# zzh.net
KiCad netlist of a schematic drawn in EAGLE
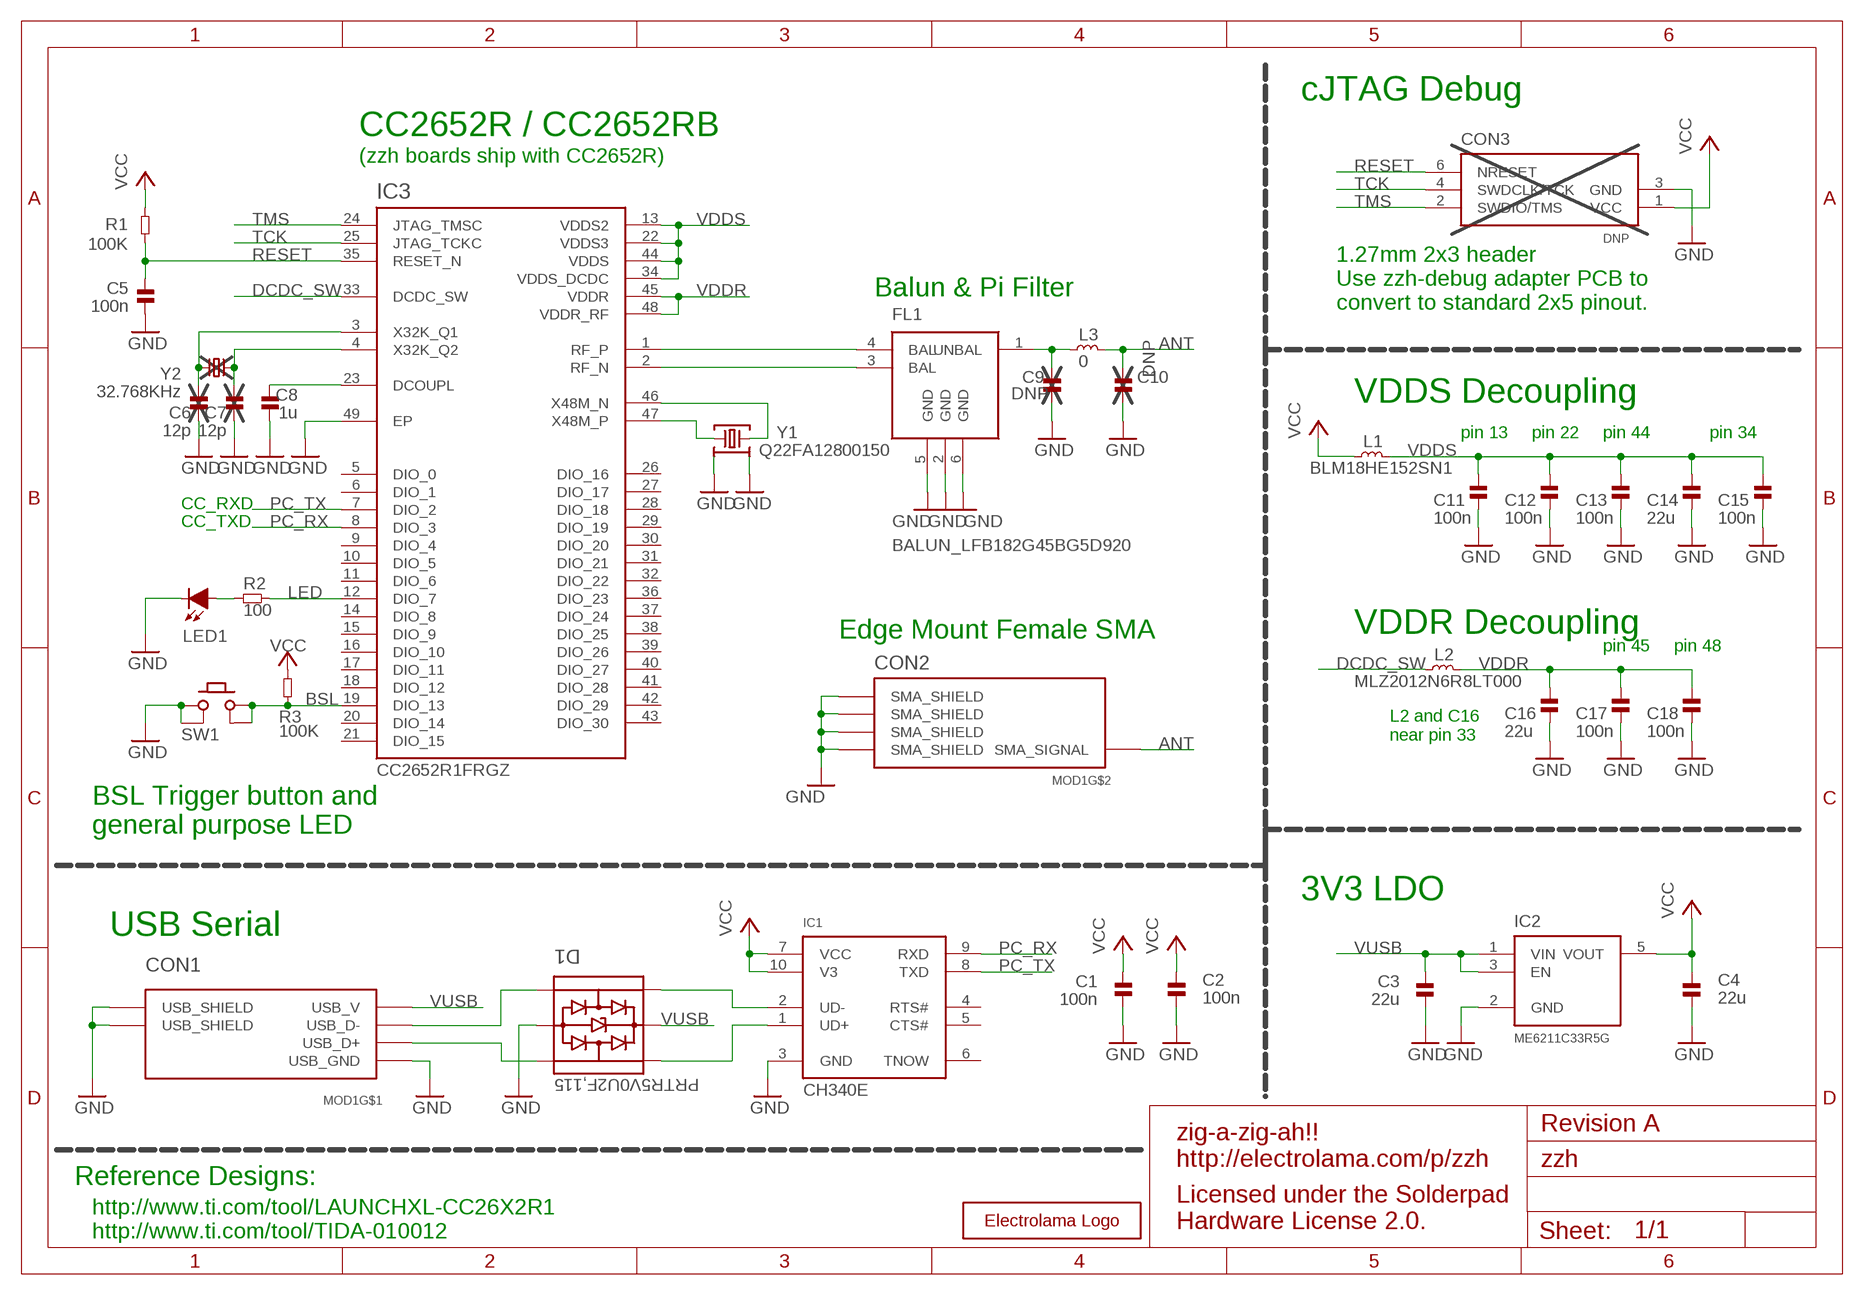
[diagram p0: schematic, sheet 1]

(export (version "E")
  (design (tool "Eeschema 10.0.6"))
  (components
    (comp (ref "C1")
      (value "100n")
      (footprint "eagle-import:_PKG_C_0402")
      (libsource (lib "eagle-import") (part "CAP-0402"))
    )
    (comp (ref "C2")
      (value "100n")
      (footprint "eagle-import:_PKG_C_0402")
      (libsource (lib "eagle-import") (part "CAP-0402"))
    )
    (comp (ref "C3")
      (value "22u")
      (footprint "eagle-import:_PKG_C_0805")
      (libsource (lib "eagle-import") (part "CAP-0805"))
    )
    (comp (ref "C4")
      (value "22u")
      (footprint "eagle-import:_PKG_C_0805")
      (libsource (lib "eagle-import") (part "CAP-0805"))
    )
    (comp (ref "C5")
      (value "100n")
      (footprint "eagle-import:_PKG_C_0402")
      (libsource (lib "eagle-import") (part "CAP-0402"))
    )
    (comp (ref "C6")
      (value "12p")
      (footprint "eagle-import:_PKG_C_0402")
      (libsource (lib "eagle-import") (part "CAP-0402"))
    )
    (comp (ref "C7")
      (value "12p")
      (footprint "eagle-import:_PKG_C_0402")
      (libsource (lib "eagle-import") (part "CAP-0402"))
    )
    (comp (ref "C8")
      (value "1u")
      (footprint "eagle-import:_PKG_C_0402")
      (libsource (lib "eagle-import") (part "CAP-0402"))
    )
    (comp (ref "C9")
      (value "DNP")
      (footprint "eagle-import:_PKG_C_0402")
      (libsource (lib "eagle-import") (part "CAP-0402"))
    )
    (comp (ref "C10")
      (value "DNP")
      (footprint "eagle-import:_PKG_C_0402")
      (libsource (lib "eagle-import") (part "CAP-0402"))
    )
    (comp (ref "C11")
      (value "100n")
      (footprint "eagle-import:_PKG_C_0402")
      (libsource (lib "eagle-import") (part "CAP-0402"))
    )
    (comp (ref "C12")
      (value "100n")
      (footprint "eagle-import:_PKG_C_0402")
      (libsource (lib "eagle-import") (part "CAP-0402"))
    )
    (comp (ref "C13")
      (value "100n")
      (footprint "eagle-import:_PKG_C_0402")
      (libsource (lib "eagle-import") (part "CAP-0402"))
    )
    (comp (ref "C14")
      (value "22u")
      (footprint "eagle-import:_PKG_C_0805")
      (libsource (lib "eagle-import") (part "CAP-0805"))
    )
    (comp (ref "C15")
      (value "100n")
      (footprint "eagle-import:_PKG_C_0402")
      (libsource (lib "eagle-import") (part "CAP-0402"))
    )
    (comp (ref "C16")
      (value "22u")
      (footprint "eagle-import:_PKG_C_0805")
      (libsource (lib "eagle-import") (part "CAP-0805"))
    )
    (comp (ref "C17")
      (value "100n")
      (footprint "eagle-import:_PKG_C_0402")
      (libsource (lib "eagle-import") (part "CAP-0402"))
    )
    (comp (ref "C18")
      (value "100n")
      (footprint "eagle-import:_PKG_C_0402")
      (libsource (lib "eagle-import") (part "CAP-0402"))
    )
    (comp (ref "CON3")
      (value "DNP")
      (footprint "eagle-import:DEBUG_CORTEX_5PIN")
      (libsource (lib "eagle-import") (part "DEBUG_CORTEX-SWD/CJTAG-5PIN-CUT5"))
    )
    (comp (ref "D1")
      (value "PRTR5V0U2F,115")
      (footprint "eagle-import:_PKG_SOT886_JEDEC-MO-252")
      (fields
        (field (name "MOUSER_PART_NUMBER") "771-PRTR5V0U2F-T/R")
        (field (name "RS_PART_NUMBER") "8166931P")
      )
      (libsource (lib "eagle-import") (part "DIODE-TVS-PRTR5V0U2F{dblquote}"))
    )
    (comp (ref "FL1")
      (value "BALUN_LFB182G45BG5D920")
      (footprint "eagle-import:LFB182G45BG5D920")
      (fields
        (field (name "MANUFACTURER_PART_NUMBER") "LFB182G45BG5D920")
        (field (name "MOUSER_PART_NUMBER") "81-LFB182G45BG5D920")
      )
      (libsource (lib "eagle-import") (part "BALUN_LFB182G45BG5D920"))
    )
    (comp (ref "IC1")
      (value "CH340E")
      (footprint "eagle-import:_PKG_MSOP10_TI-DGS10")
      (libsource (lib "eagle-import") (part "INTERFACE-CH340E"))
    )
    (comp (ref "IC2")
      (value "ME6211C33R5G")
      (footprint "eagle-import:SOT65P212X110-5N")
      (libsource (lib "eagle-import") (part "POWER-LDO-ME6211C33R5G"))
    )
    (comp (ref "IC3")
      (value "CC2652R1FRGZ")
      (footprint "eagle-import:QFN50P700X700X100-49N")
      (fields
        (field (name "MANUFACTURER_PART_NUMBER") "CC2652R1FRGZT")
        (field (name "MOUSER_PART_NUMBER") "595-CC2652R1FRGZT")
      )
      (libsource (lib "eagle-import") (part "WMCU-CC2652R1FRGZ"))
    )
    (comp (ref "L1")
      (value "BLM18HE152SN1")
      (footprint "eagle-import:_PKG_L_0603")
      (libsource (lib "eagle-import") (part "INDUCTOR-0603"))
    )
    (comp (ref "L2")
      (value "MLZ2012N6R8LT000")
      (footprint "eagle-import:_PKG_C_0805")
      (libsource (lib "eagle-import") (part "INDUCTOR-0805"))
    )
    (comp (ref "L3")
      (value "0")
      (footprint "eagle-import:_PKG_L_0402")
      (libsource (lib "eagle-import") (part "INDUCTOR-0402"))
    )
    (comp (ref "LED1")
      (value "LED-0603")
      (footprint "eagle-import:_PKG_LED_0603")
      (libsource (lib "eagle-import") (part "LED-0603"))
    )
    (comp (ref "MOD1")
      (value "ZZH_MODULE")
      (footprint "eagle-import:ZZH_MODULE")
      (libsource (lib "eagle-import") (part "ZZH_MODULE"))
    )
    (comp (ref "R1")
      (value "100K")
      (footprint "eagle-import:_PKG_C_0402")
      (libsource (lib "eagle-import") (part "RES-0402"))
    )
    (comp (ref "R2")
      (value "100")
      (footprint "eagle-import:_PKG_C_0402")
      (libsource (lib "eagle-import") (part "RES-0402"))
    )
    (comp (ref "R3")
      (value "100K")
      (footprint "eagle-import:_PKG_C_0402")
      (libsource (lib "eagle-import") (part "RES-0402"))
    )
    (comp (ref "SW1")
      (value "K2-1177SW-D4DW-06")
      (footprint "eagle-import:K2-1177SW-D4DW-06")
      (libsource (lib "eagle-import") (part "PUSHBUTTON-K2-1177SW-D4DW-06"))
    )
    (comp (ref "U$5")
      (value "LOGO-ELECTROLAMA")
      (footprint "eagle-import:ELECTROLAMA")
      (libsource (lib "eagle-import") (part "LOGO-ELECTROLAMA"))
    )
    (comp (ref "Y1")
      (value "Q22FA12800150")
      (footprint "eagle-import:XTAL-4P-2016")
      (fields (field (name "DIGIKEY_PART") "1253-2042-1-ND") (field (name "MFG_PART") "CX2016DB48000C0FPLC1"))
      (libsource (lib "eagle-import") (part "48.000MHZ_CX2016DB48000C0FPLC1"))
    )
    (comp (ref "Y2")
      (value "32.768KHz")
      (footprint "eagle-import:XTAL-2P-3215")
      (fields (field (name "LCSC_PART") "C32346") (field (name "MFG_PART") "Q13FC1350000400"))
      (libsource (lib "eagle-import") (part "32.768KHZ_Q13FC1350000400"))
    )
  )
  (nets
    (net (code "1") (name "/ANT") (class "Default")
      (node (ref "C10") (pin "2") (pinfunction "2_2") (pintype "passive"))
      (node (ref "L3") (pin "2") (pinfunction "2_2") (pintype "passive"))
      (node (ref "MOD1") (pin "SMA_SIGNAL") (pinfunction "SMA_SIGNAL_SMA_SIGNAL") (pintype "bidirectional"))
    )
    (net (code "2") (name "/BSL") (class "Default")
      (node (ref "IC3") (pin "19") (pinfunction "DIO_13_19") (pintype "bidirectional"))
      (node (ref "R3") (pin "2") (pinfunction "2_2") (pintype "passive"))
      (node (ref "SW1") (pin "3") (pinfunction "2_1_3") (pintype "bidirectional"))
      (node (ref "SW1") (pin "4") (pinfunction "2_2_4") (pintype "bidirectional"))
    )
    (net (code "3") (name "/DCDC_SW") (class "Default")
      (node (ref "IC3") (pin "33") (pinfunction "DCDC_SW_33") (pintype "bidirectional"))
      (node (ref "L2") (pin "1") (pinfunction "1_1") (pintype "passive"))
    )
    (net (code "4") (name "/LED") (class "Default")
      (node (ref "IC3") (pin "12") (pinfunction "DIO_7_12") (pintype "bidirectional"))
      (node (ref "R2") (pin "1") (pinfunction "1_1") (pintype "passive"))
    )
    (net (code "5") (name "/PC_RX") (class "Default")
      (node (ref "IC1") (pin "9") (pinfunction "RXD_9") (pintype "bidirectional"))
      (node (ref "IC3") (pin "8") (pinfunction "DIO_3_8") (pintype "bidirectional"))
    )
    (net (code "6") (name "/PC_TX") (class "Default")
      (node (ref "IC1") (pin "8") (pinfunction "TXD_8") (pintype "bidirectional"))
      (node (ref "IC3") (pin "7") (pinfunction "DIO_2_7") (pintype "bidirectional"))
    )
    (net (code "7") (name "/RESET") (class "Default")
      (node (ref "C5") (pin "2") (pinfunction "2_2") (pintype "passive"))
      (node (ref "CON3") (pin "6") (pinfunction "NRESET_6") (pintype "bidirectional"))
      (node (ref "IC3") (pin "35") (pinfunction "RESET_N_35") (pintype "bidirectional"))
      (node (ref "R1") (pin "1") (pinfunction "1_1") (pintype "passive"))
    )
    (net (code "8") (name "/TCK") (class "Default")
      (node (ref "CON3") (pin "4") (pinfunction "SWDCLK/TCK_4") (pintype "bidirectional"))
      (node (ref "IC3") (pin "25") (pinfunction "JTAG_TCKC_25") (pintype "bidirectional"))
    )
    (net (code "9") (name "/TMS") (class "Default")
      (node (ref "CON3") (pin "2") (pinfunction "SWDIO/TMS_2") (pintype "bidirectional"))
      (node (ref "IC3") (pin "24") (pinfunction "JTAG_TMSC_24") (pintype "bidirectional"))
    )
    (net (code "10") (name "/VDDR") (class "Default")
      (node (ref "C16") (pin "1") (pinfunction "1_1") (pintype "passive"))
      (node (ref "C17") (pin "1") (pinfunction "1_1") (pintype "passive"))
      (node (ref "C18") (pin "1") (pinfunction "1_1") (pintype "passive"))
      (node (ref "IC3") (pin "45") (pinfunction "VDDR_45") (pintype "bidirectional"))
      (node (ref "IC3") (pin "48") (pinfunction "VDDR_RF_48") (pintype "bidirectional"))
      (node (ref "L2") (pin "2") (pinfunction "2_2") (pintype "passive"))
    )
    (net (code "11") (name "/VDDS") (class "Default")
      (node (ref "C11") (pin "1") (pinfunction "1_1") (pintype "passive"))
      (node (ref "C12") (pin "1") (pinfunction "1_1") (pintype "passive"))
      (node (ref "C13") (pin "1") (pinfunction "1_1") (pintype "passive"))
      (node (ref "C14") (pin "1") (pinfunction "1_1") (pintype "passive"))
      (node (ref "C15") (pin "1") (pinfunction "1_1") (pintype "passive"))
      (node (ref "IC3") (pin "13") (pinfunction "VDDS2_13") (pintype "bidirectional"))
      (node (ref "IC3") (pin "22") (pinfunction "VDDS3_22") (pintype "bidirectional"))
      (node (ref "IC3") (pin "34") (pinfunction "VDDS_DCDC_34") (pintype "bidirectional"))
      (node (ref "IC3") (pin "44") (pinfunction "VDDS_44") (pintype "bidirectional"))
      (node (ref "L1") (pin "2") (pinfunction "2_2") (pintype "passive"))
    )
    (net (code "12") (name "/VUSB") (class "Default")
      (node (ref "C3") (pin "1") (pinfunction "1_1") (pintype "passive"))
      (node (ref "D1") (pin "5") (pinfunction "5_5") (pintype "passive"))
      (node (ref "IC2") (pin "1") (pinfunction "VIN_1") (pintype "bidirectional"))
      (node (ref "IC2") (pin "3") (pinfunction "EN_3") (pintype "bidirectional"))
      (node (ref "MOD1") (pin "USB_V") (pinfunction "USB_V_USB_V") (pintype "bidirectional"))
    )
    (net (code "13") (name "GND") (class "Default")
      (node (ref "C1") (pin "1") (pinfunction "1_1") (pintype "passive"))
      (node (ref "C10") (pin "1") (pinfunction "1_1") (pintype "passive"))
      (node (ref "C11") (pin "2") (pinfunction "2_2") (pintype "passive"))
      (node (ref "C12") (pin "2") (pinfunction "2_2") (pintype "passive"))
      (node (ref "C13") (pin "2") (pinfunction "2_2") (pintype "passive"))
      (node (ref "C14") (pin "2") (pinfunction "2_2") (pintype "passive"))
      (node (ref "C15") (pin "2") (pinfunction "2_2") (pintype "passive"))
      (node (ref "C16") (pin "2") (pinfunction "2_2") (pintype "passive"))
      (node (ref "C17") (pin "2") (pinfunction "2_2") (pintype "passive"))
      (node (ref "C18") (pin "2") (pinfunction "2_2") (pintype "passive"))
      (node (ref "C2") (pin "1") (pinfunction "1_1") (pintype "passive"))
      (node (ref "C3") (pin "2") (pinfunction "2_2") (pintype "passive"))
      (node (ref "C4") (pin "2") (pinfunction "2_2") (pintype "passive"))
      (node (ref "C5") (pin "1") (pinfunction "1_1") (pintype "passive"))
      (node (ref "C6") (pin "1") (pinfunction "1_1") (pintype "passive"))
      (node (ref "C7") (pin "1") (pinfunction "1_1") (pintype "passive"))
      (node (ref "C8") (pin "1") (pinfunction "1_1") (pintype "passive"))
      (node (ref "C9") (pin "1") (pinfunction "1_1") (pintype "passive"))
      (node (ref "CON3") (pin "3") (pinfunction "GND_3") (pintype "bidirectional"))
      (node (ref "D1") (pin "2") (pinfunction "2_2") (pintype "passive"))
      (node (ref "FL1") (pin "2") (pinfunction "GND_2") (pintype "bidirectional"))
      (node (ref "FL1") (pin "5") (pinfunction "GND_5") (pintype "bidirectional"))
      (node (ref "FL1") (pin "6") (pinfunction "GND_6") (pintype "bidirectional"))
      (node (ref "IC1") (pin "3") (pinfunction "GND_3") (pintype "bidirectional"))
      (node (ref "IC2") (pin "2") (pinfunction "GND_2") (pintype "bidirectional"))
      (node (ref "IC3") (pin "49") (pinfunction "EP_49") (pintype "bidirectional"))
      (node (ref "LED1") (pin "C") (pinfunction "C_C") (pintype "passive"))
      (node (ref "MOD1") (pin "SMA_SHIELD_1") (pinfunction "SMA_SHIELD_SMA_SHIELD_1") (pintype "bidirectional"))
      (node (ref "MOD1") (pin "SMA_SHIELD_2") (pinfunction "SMA_SHIELD_SMA_SHIELD_2") (pintype "bidirectional"))
      (node (ref "MOD1") (pin "SMA_SHIELD_3") (pinfunction "SMA_SHIELD_SMA_SHIELD_3") (pintype "bidirectional"))
      (node (ref "MOD1") (pin "SMA_SHIELD_4") (pinfunction "SMA_SHIELD_SMA_SHIELD_4") (pintype "bidirectional"))
      (node (ref "MOD1") (pin "USB_GND") (pinfunction "USB_GND_USB_GND") (pintype "bidirectional"))
      (node (ref "MOD1") (pin "USB_SHIELD_1") (pinfunction "USB_SHIELD_USB_SHIELD_1") (pintype "bidirectional"))
      (node (ref "MOD1") (pin "USB_SHIELD_2") (pinfunction "USB_SHIELD_USB_SHIELD_2") (pintype "bidirectional"))
      (node (ref "SW1") (pin "1") (pinfunction "1_1_1") (pintype "bidirectional"))
      (node (ref "SW1") (pin "2") (pinfunction "1_2_2") (pintype "bidirectional"))
      (node (ref "Y1") (pin "2") (pinfunction "2_2") (pintype "bidirectional"))
      (node (ref "Y1") (pin "4") (pinfunction "4_4") (pintype "bidirectional"))
    )
    (net (code "14") (name "Net-(D1-Pad1)") (class "Default")
      (node (ref "D1") (pin "1") (pinfunction "1_1") (pintype "passive"))
      (node (ref "MOD1") (pin "USB_D+") (pinfunction "USB_D+_USB_D+") (pintype "bidirectional"))
    )
    (net (code "15") (name "Net-(D1-Pad3)") (class "Default")
      (node (ref "D1") (pin "3") (pinfunction "3_3") (pintype "passive"))
      (node (ref "MOD1") (pin "USB_D-") (pinfunction "USB_D-_USB_D-") (pintype "bidirectional"))
    )
    (net (code "16") (name "Net-(FL1-UNBAL)") (class "Default")
      (node (ref "C9") (pin "2") (pinfunction "2_2") (pintype "passive"))
      (node (ref "FL1") (pin "1") (pinfunction "UNBAL_1") (pintype "bidirectional"))
      (node (ref "L3") (pin "1") (pinfunction "1_1") (pintype "passive"))
    )
    (net (code "17") (name "Net-(IC1-UD+)") (class "Default")
      (node (ref "D1") (pin "6") (pinfunction "6_6") (pintype "passive"))
      (node (ref "IC1") (pin "1") (pinfunction "UD+_1") (pintype "bidirectional"))
    )
    (net (code "18") (name "Net-(IC1-UD-)") (class "Default")
      (node (ref "D1") (pin "4") (pinfunction "4_4") (pintype "passive"))
      (node (ref "IC1") (pin "2") (pinfunction "UD-_2") (pintype "bidirectional"))
    )
    (net (code "19") (name "Net-(IC3-DCOUPL)") (class "Default")
      (node (ref "C8") (pin "2") (pinfunction "2_2") (pintype "passive"))
      (node (ref "IC3") (pin "23") (pinfunction "DCOUPL_23") (pintype "bidirectional"))
    )
    (net (code "20") (name "Net-(IC3-RF_N)") (class "Default")
      (node (ref "FL1") (pin "3") (pinfunction "BAL_3") (pintype "bidirectional"))
      (node (ref "IC3") (pin "2") (pinfunction "RF_N_2") (pintype "bidirectional"))
    )
    (net (code "21") (name "Net-(IC3-RF_P)") (class "Default")
      (node (ref "FL1") (pin "4") (pinfunction "BAL_4") (pintype "bidirectional"))
      (node (ref "IC3") (pin "1") (pinfunction "RF_P_1") (pintype "bidirectional"))
    )
    (net (code "22") (name "Net-(IC3-X32K_Q1)") (class "Default")
      (node (ref "C6") (pin "2") (pinfunction "2_2") (pintype "passive"))
      (node (ref "IC3") (pin "3") (pinfunction "X32K_Q1_3") (pintype "bidirectional"))
      (node (ref "Y2") (pin "1") (pinfunction "1_1") (pintype "passive"))
    )
    (net (code "23") (name "Net-(IC3-X32K_Q2)") (class "Default")
      (node (ref "C7") (pin "2") (pinfunction "2_2") (pintype "passive"))
      (node (ref "IC3") (pin "4") (pinfunction "X32K_Q2_4") (pintype "bidirectional"))
      (node (ref "Y2") (pin "2") (pinfunction "2_2") (pintype "passive"))
    )
    (net (code "24") (name "Net-(IC3-X48M_N)") (class "Default")
      (node (ref "IC3") (pin "46") (pinfunction "X48M_N_46") (pintype "bidirectional"))
      (node (ref "Y1") (pin "3") (pinfunction "3_3") (pintype "passive"))
    )
    (net (code "25") (name "Net-(IC3-X48M_P)") (class "Default")
      (node (ref "IC3") (pin "47") (pinfunction "X48M_P_47") (pintype "bidirectional"))
      (node (ref "Y1") (pin "1") (pinfunction "1_1") (pintype "passive"))
    )
    (net (code "26") (name "Net-(LED1-PadA)") (class "Default")
      (node (ref "LED1") (pin "A") (pinfunction "A_A") (pintype "passive"))
      (node (ref "R2") (pin "2") (pinfunction "2_2") (pintype "passive"))
    )
    (net (code "27") (name "VCC") (class "Default")
      (node (ref "C1") (pin "2") (pinfunction "2_2") (pintype "passive"))
      (node (ref "C2") (pin "2") (pinfunction "2_2") (pintype "passive"))
      (node (ref "C4") (pin "1") (pinfunction "1_1") (pintype "passive"))
      (node (ref "CON3") (pin "1") (pinfunction "VCC_1") (pintype "bidirectional"))
      (node (ref "IC1") (pin "10") (pinfunction "V3_10") (pintype "bidirectional"))
      (node (ref "IC1") (pin "7") (pinfunction "VCC_7") (pintype "bidirectional"))
      (node (ref "IC2") (pin "5") (pinfunction "VOUT_5") (pintype "bidirectional"))
      (node (ref "L1") (pin "1") (pinfunction "1_1") (pintype "passive"))
      (node (ref "R1") (pin "2") (pinfunction "2_2") (pintype "passive"))
      (node (ref "R3") (pin "1") (pinfunction "1_1") (pintype "passive"))
    )
    (net (code "28") (name "unconnected-(IC1-CTS#-Pad5)") (class "Default")
      (node (ref "IC1") (pin "5") (pinfunction "CTS#_5") (pintype "bidirectional"))
    )
    (net (code "29") (name "unconnected-(IC1-RTS#-Pad4)") (class "Default")
      (node (ref "IC1") (pin "4") (pinfunction "RTS#_4") (pintype "bidirectional"))
    )
    (net (code "30") (name "unconnected-(IC1-TNOW-Pad6)") (class "Default")
      (node (ref "IC1") (pin "6") (pinfunction "TNOW_6") (pintype "bidirectional"))
    )
    (net (code "31") (name "unconnected-(IC3-DIO_0-Pad5)") (class "Default")
      (node (ref "IC3") (pin "5") (pinfunction "DIO_0_5") (pintype "bidirectional"))
    )
    (net (code "32") (name "unconnected-(IC3-DIO_1-Pad6)") (class "Default")
      (node (ref "IC3") (pin "6") (pinfunction "DIO_1_6") (pintype "bidirectional"))
    )
    (net (code "33") (name "unconnected-(IC3-DIO_4-Pad9)") (class "Default")
      (node (ref "IC3") (pin "9") (pinfunction "DIO_4_9") (pintype "bidirectional"))
    )
    (net (code "34") (name "unconnected-(IC3-DIO_5-Pad10)") (class "Default")
      (node (ref "IC3") (pin "10") (pinfunction "DIO_5_10") (pintype "bidirectional"))
    )
    (net (code "35") (name "unconnected-(IC3-DIO_6-Pad11)") (class "Default")
      (node (ref "IC3") (pin "11") (pinfunction "DIO_6_11") (pintype "bidirectional"))
    )
    (net (code "36") (name "unconnected-(IC3-DIO_8-Pad14)") (class "Default")
      (node (ref "IC3") (pin "14") (pinfunction "DIO_8_14") (pintype "bidirectional"))
    )
    (net (code "37") (name "unconnected-(IC3-DIO_9-Pad15)") (class "Default")
      (node (ref "IC3") (pin "15") (pinfunction "DIO_9_15") (pintype "bidirectional"))
    )
    (net (code "38") (name "unconnected-(IC3-DIO_10-Pad16)") (class "Default")
      (node (ref "IC3") (pin "16") (pinfunction "DIO_10_16") (pintype "bidirectional"))
    )
    (net (code "39") (name "unconnected-(IC3-DIO_11-Pad17)") (class "Default")
      (node (ref "IC3") (pin "17") (pinfunction "DIO_11_17") (pintype "bidirectional"))
    )
    (net (code "40") (name "unconnected-(IC3-DIO_12-Pad18)") (class "Default")
      (node (ref "IC3") (pin "18") (pinfunction "DIO_12_18") (pintype "bidirectional"))
    )
    (net (code "41") (name "unconnected-(IC3-DIO_14-Pad20)") (class "Default")
      (node (ref "IC3") (pin "20") (pinfunction "DIO_14_20") (pintype "bidirectional"))
    )
    (net (code "42") (name "unconnected-(IC3-DIO_15-Pad21)") (class "Default")
      (node (ref "IC3") (pin "21") (pinfunction "DIO_15_21") (pintype "bidirectional"))
    )
    (net (code "43") (name "unconnected-(IC3-DIO_16-Pad26)") (class "Default")
      (node (ref "IC3") (pin "26") (pinfunction "DIO_16_26") (pintype "bidirectional"))
    )
    (net (code "44") (name "unconnected-(IC3-DIO_17-Pad27)") (class "Default")
      (node (ref "IC3") (pin "27") (pinfunction "DIO_17_27") (pintype "bidirectional"))
    )
    (net (code "45") (name "unconnected-(IC3-DIO_18-Pad28)") (class "Default")
      (node (ref "IC3") (pin "28") (pinfunction "DIO_18_28") (pintype "bidirectional"))
    )
    (net (code "46") (name "unconnected-(IC3-DIO_19-Pad29)") (class "Default")
      (node (ref "IC3") (pin "29") (pinfunction "DIO_19_29") (pintype "bidirectional"))
    )
    (net (code "47") (name "unconnected-(IC3-DIO_20-Pad30)") (class "Default")
      (node (ref "IC3") (pin "30") (pinfunction "DIO_20_30") (pintype "bidirectional"))
    )
    (net (code "48") (name "unconnected-(IC3-DIO_21-Pad31)") (class "Default")
      (node (ref "IC3") (pin "31") (pinfunction "DIO_21_31") (pintype "bidirectional"))
    )
    (net (code "49") (name "unconnected-(IC3-DIO_22-Pad32)") (class "Default")
      (node (ref "IC3") (pin "32") (pinfunction "DIO_22_32") (pintype "bidirectional"))
    )
    (net (code "50") (name "unconnected-(IC3-DIO_23-Pad36)") (class "Default")
      (node (ref "IC3") (pin "36") (pinfunction "DIO_23_36") (pintype "bidirectional"))
    )
    (net (code "51") (name "unconnected-(IC3-DIO_24-Pad37)") (class "Default")
      (node (ref "IC3") (pin "37") (pinfunction "DIO_24_37") (pintype "bidirectional"))
    )
    (net (code "52") (name "unconnected-(IC3-DIO_25-Pad38)") (class "Default")
      (node (ref "IC3") (pin "38") (pinfunction "DIO_25_38") (pintype "bidirectional"))
    )
    (net (code "53") (name "unconnected-(IC3-DIO_26-Pad39)") (class "Default")
      (node (ref "IC3") (pin "39") (pinfunction "DIO_26_39") (pintype "bidirectional"))
    )
    (net (code "54") (name "unconnected-(IC3-DIO_27-Pad40)") (class "Default")
      (node (ref "IC3") (pin "40") (pinfunction "DIO_27_40") (pintype "bidirectional"))
    )
    (net (code "55") (name "unconnected-(IC3-DIO_28-Pad41)") (class "Default")
      (node (ref "IC3") (pin "41") (pinfunction "DIO_28_41") (pintype "bidirectional"))
    )
    (net (code "56") (name "unconnected-(IC3-DIO_29-Pad42)") (class "Default")
      (node (ref "IC3") (pin "42") (pinfunction "DIO_29_42") (pintype "bidirectional"))
    )
    (net (code "57") (name "unconnected-(IC3-DIO_30-Pad43)") (class "Default")
      (node (ref "IC3") (pin "43") (pinfunction "DIO_30_43") (pintype "bidirectional"))
    )
  )
)
